# 04_DragonBoard_INTF.net
KiCad netlist of a schematic drawn in Altium Designer
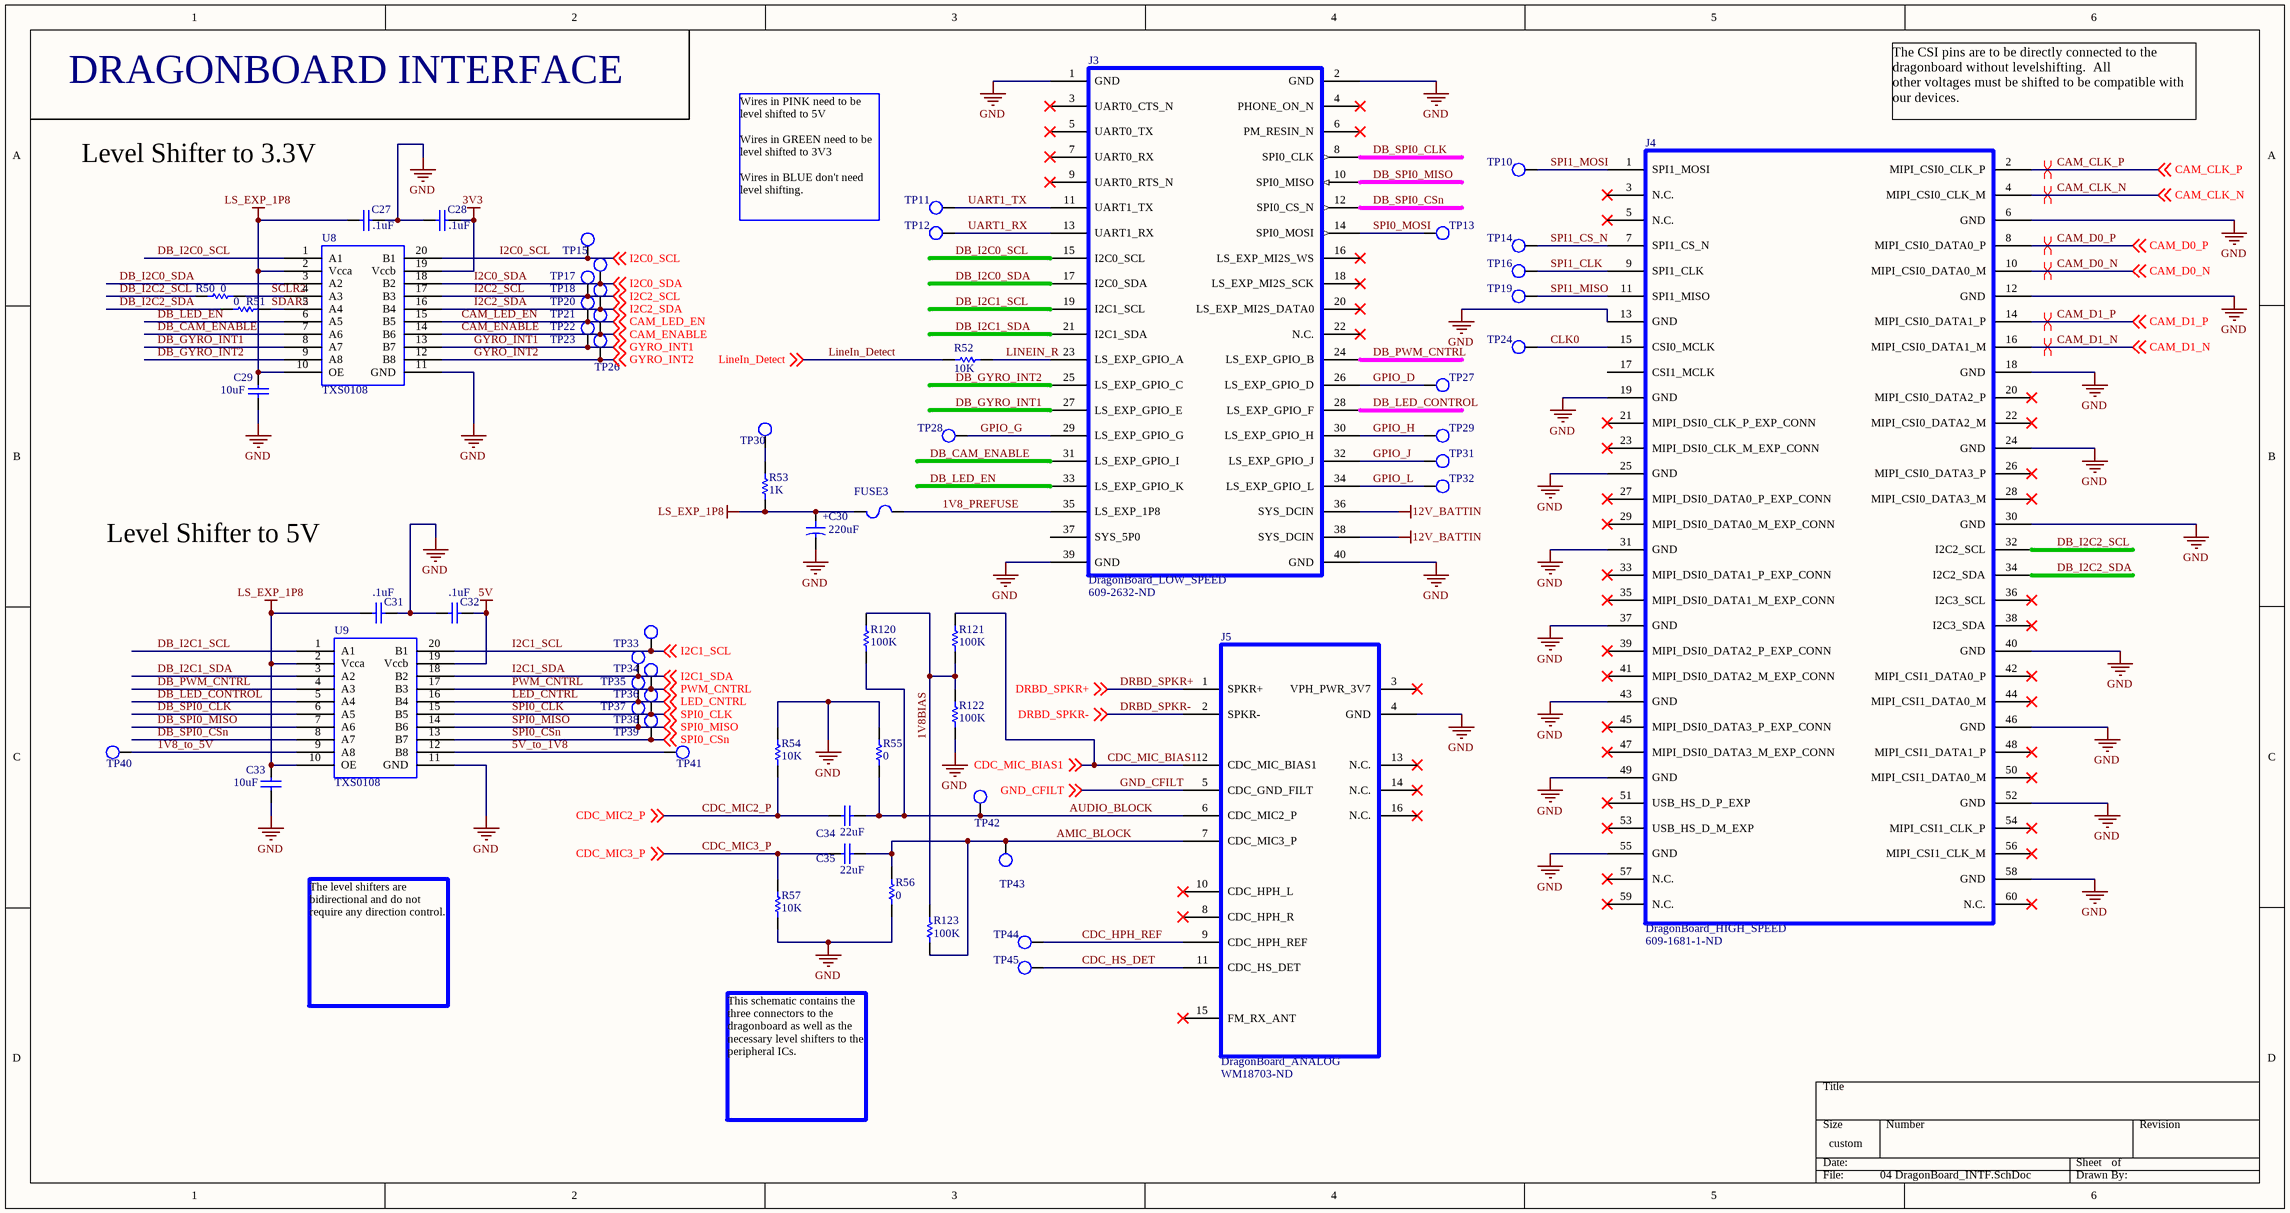
[diagram p0: 04 DragonBoard_INTF.SchDoc]

(export (version "E")
  (design (tool "Eeschema 10.0.6"))
  (components
    (comp (ref "C27")
      (value ".1uF")
      (footprint "CAPC2012X135N")
      (description "Cap Ceramic 0.1uF 250V X7T 10% SMD 0805 125C Plastic T/R")
      (fields
        (field (name "MANUFACTURER") "TDK")
        (field (name "MANUFACTURER PART NUMBER") "C2012X7T2E104K125AE")
      )
      (libsource (lib "schlib_truman") (part "CAP_0805_.1u_250V"))
    )
    (comp (ref "C28")
      (value ".1uF")
      (footprint "CAPC2012X135N")
      (description "Cap Ceramic 0.1uF 250V X7T 10% SMD 0805 125C Plastic T/R")
      (fields
        (field (name "MANUFACTURER") "TDK")
        (field (name "MANUFACTURER PART NUMBER") "C2012X7T2E104K125AE")
      )
      (libsource (lib "schlib_truman") (part "CAP_0805_.1u_250V"))
    )
    (comp (ref "C29")
      (value "10uF")
      (footprint "CAPC2012X135N")
      (description "Cap Ceramic 10uF 16V X5R 10% SMD 0805 85C T/R")
      (fields
        (field (name "MANUFACTURER") "Johanson Dielectrics")
        (field (name "MANUFACTURER PART NUMBER") "160R15X106KV4E")
      )
      (libsource (lib "schlib_truman") (part "CAP_0805_10u_16V"))
    )
    (comp (ref "C30")
      (value "CAP ALUM 220UF 20% 25V SMD")
      (footprint "CAP_RADIAL")
      (fields
        (field (name "MANUFACTURER") "Nichicon")
        (field (name "MANUFACTURER PART NUMBER") "UWT1E221MNL1GS")
        (field (name "TOLERANCE") "20%")
        (field (name "CAPACITANCE") "220uF")
      )
      (libsource (lib "schlib_truman") (part "CAP_RAD_220u_25V"))
    )
    (comp (ref "C31")
      (value ".1uF")
      (footprint "CAPC2012X135N")
      (description "Cap Ceramic 0.1uF 250V X7T 10% SMD 0805 125C Plastic T/R")
      (fields
        (field (name "MANUFACTURER") "TDK")
        (field (name "MANUFACTURER PART NUMBER") "C2012X7T2E104K125AE")
      )
      (libsource (lib "schlib_truman") (part "CAP_0805_.1u_250V"))
    )
    (comp (ref "C32")
      (value ".1uF")
      (footprint "CAPC2012X135N")
      (description "Cap Ceramic 0.1uF 250V X7T 10% SMD 0805 125C Plastic T/R")
      (fields
        (field (name "MANUFACTURER") "TDK")
        (field (name "MANUFACTURER PART NUMBER") "C2012X7T2E104K125AE")
      )
      (libsource (lib "schlib_truman") (part "CAP_0805_.1u_250V"))
    )
    (comp (ref "C33")
      (value "10uF")
      (footprint "CAPC2012X135N")
      (description "Cap Ceramic 10uF 16V X5R 10% SMD 0805 85C T/R")
      (fields
        (field (name "MANUFACTURER") "Johanson Dielectrics")
        (field (name "MANUFACTURER PART NUMBER") "160R15X106KV4E")
      )
      (libsource (lib "schlib_truman") (part "CAP_0805_10u_16V"))
    )
    (comp (ref "C34")
      (value "22uF")
      (footprint "CAPC2012X135N")
      (fields
        (field (name "MANUFACTURER") "Samsung")
        (field (name "MANUFACTURER PART NUMBER") "CL21A226MAQNNNE")
        (field (name "TOLERANCE") "20%")
      )
      (libsource (lib "schlib_truman") (part "CAP_0805_22u_25V"))
    )
    (comp (ref "C35")
      (value "22uF")
      (footprint "CAPC2012X135N")
      (fields
        (field (name "MANUFACTURER") "Samsung")
        (field (name "MANUFACTURER PART NUMBER") "CL21A226MAQNNNE")
        (field (name "TOLERANCE") "20%")
      )
      (libsource (lib "schlib_truman") (part "CAP_0805_22u_25V"))
    )
    (comp (ref "FUSE3")
      (value "FUSE_0805_1A_32VDC")
      (footprint "RES0805")
      (description "FUSE 1.00A 0805 VFAST SMD")
      (fields
        (field (name "MANUFACTURER") "Vishay")
        (field (name "MANUFACTURER PART NUMBER") "MFU0805FF01000P100")
      )
      (libsource (lib "schlib_truman") (part "FUSE_0805_1A_32VDC"))
    )
    (comp (ref "J3")
      (value "DragonBoard_LOW_SPEED")
      (footprint "57202_40_PIN_HEADER")
      (description "40 Positions Header, Unshrouded Connector 0.079\" (2.00mm) Surface Mount Gold, GXT™")
      (fields
        (field (name "MANUFACTURER") "Amphenol FCI")
        (field (name "MANUFACTURER PART NUMBER") "57202-G52-20LF")
        (field (name "SUPPLIER PART NUMBER 1") "609-2632-ND")
      )
      (libsource (lib "schlib_truman") (part "DragonBoard_LOW_SPEED"))
    )
    (comp (ref "J4")
      (value "DragonBoard_HIGH_SPEED")
      (footprint "DB_HIGH_SPEED")
      (description "60 Position Connector Plug, Center Strip Contacts Surface Mount Gold")
      (fields
        (field (name "MANUFACTURER") "Amphenol FCI")
        (field (name "MANUFACTURER PART NUMBER") "61083-064402LF")
        (field (name "SUPPLIER PART NUMBER 1") "609-1681-1-ND")
      )
      (libsource (lib "schlib_truman") (part "DragonBoard_HIGH_SPEED"))
    )
    (comp (ref "J5")
      (value "DragonBoard_ANALOG")
      (footprint "16_PIN_ANALOG_CONN")
      (description "Conn Socket Strip RCP 16 POS 2mm Solder ST SMD Tube")
      (fields
        (field (name "MANUFACTURER") "Molex")
        (field (name "MANUFACTURER PART NUMBER") "0791091007")
        (field (name "SUPPLIER PART NUMBER 1") "WM18703-ND")
      )
      (libsource (lib "schlib_truman") (part "DragonBoard_ANALOG"))
    )
    (comp (ref "R50")
      (value "RES_0805_JMP")
      (footprint "RES0805")
      (description "RES, THICK FILM, 0R, 0.125W, 0805")
      (fields
        (field (name "MANUFACTURER") "Yageo")
        (field (name "MANUFACTURER PART NUMBER") "RC0805JR-070RL")
        (field (name "ALTIUM_UNNAMED_1") "0")
      )
      (libsource (lib "schlib_truman") (part "RES_0805_JMP"))
    )
    (comp (ref "R51")
      (value "RES_0805_JMP")
      (footprint "RES0805")
      (description "RES, THICK FILM, 0R, 0.125W, 0805")
      (fields
        (field (name "MANUFACTURER") "Yageo")
        (field (name "MANUFACTURER PART NUMBER") "RC0805JR-070RL")
        (field (name "ALTIUM_UNNAMED_1") "0")
      )
      (libsource (lib "schlib_truman") (part "RES_0805_JMP"))
    )
    (comp (ref "R52")
      (value "RES_0805_10K")
      (footprint "RES0805")
      (description "RES, THICK FILM, 10K, 5%, 0.125W, 0805")
      (fields
        (field (name "MANUFACTURER") "Yageo")
        (field (name "MANUFACTURER PART NUMBER") "RC0805JR-0710KL")
        (field (name "RESISTANCE") "10K")
      )
      (libsource (lib "schlib_truman") (part "RES_0805_10K"))
    )
    (comp (ref "R53")
      (value "RES_0805_1K")
      (footprint "RES0805")
      (description "RES SMD 1K OHM 1% 1/8W 0805")
      (fields
        (field (name "MANUFACTURER") "Yageo")
        (field (name "MANUFACTURER PART NUMBER") "RC0805FR-071KL")
        (field (name "ALTIUM_UNNAMED_1") "1K")
      )
      (libsource (lib "schlib_truman") (part "RES_0805_1K"))
    )
    (comp (ref "R54")
      (value "RES_0805_10K")
      (footprint "RES0805")
      (description "RES, THICK FILM, 10K, 5%, 0.125W, 0805")
      (fields
        (field (name "MANUFACTURER") "Yageo")
        (field (name "MANUFACTURER PART NUMBER") "RC0805JR-0710KL")
        (field (name "RESISTANCE") "10K")
      )
      (libsource (lib "schlib_truman") (part "RES_0805_10K"))
    )
    (comp (ref "R55")
      (value "RES_0805_JMP")
      (footprint "RES0805")
      (description "RES, THICK FILM, 0R, 0.125W, 0805")
      (fields
        (field (name "MANUFACTURER") "Yageo")
        (field (name "MANUFACTURER PART NUMBER") "RC0805JR-070RL")
        (field (name "ALTIUM_UNNAMED_1") "0")
      )
      (libsource (lib "schlib_truman") (part "RES_0805_JMP"))
    )
    (comp (ref "R56")
      (value "RES_0805_JMP")
      (footprint "RES0805")
      (description "RES, THICK FILM, 0R, 0.125W, 0805")
      (fields
        (field (name "MANUFACTURER") "Yageo")
        (field (name "MANUFACTURER PART NUMBER") "RC0805JR-070RL")
        (field (name "ALTIUM_UNNAMED_1") "0")
      )
      (libsource (lib "schlib_truman") (part "RES_0805_JMP"))
    )
    (comp (ref "R57")
      (value "RES_0805_10K")
      (footprint "RES0805")
      (description "RES, THICK FILM, 10K, 5%, 0.125W, 0805")
      (fields
        (field (name "MANUFACTURER") "Yageo")
        (field (name "MANUFACTURER PART NUMBER") "RC0805JR-0710KL")
        (field (name "RESISTANCE") "10K")
      )
      (libsource (lib "schlib_truman") (part "RES_0805_10K"))
    )
    (comp (ref "R120")
      (value "RES_0805_100K")
      (footprint "RES0805")
      (description "Res Thick Film 0805 100K Ohm 1% 0.125W(1/8W) ±100ppm/C Molded SMD Automotive Punched T/R")
      (fields
        (field (name "MANUFACTURER") "Panasonic ECG")
        (field (name "MANUFACTURER PART NUMBER") "ERJ-6ENF1003V")
        (field (name "ALTIUM_UNNAMED_1") "100K")
      )
      (libsource (lib "schlib_truman") (part "RES_0805_100K"))
    )
    (comp (ref "R121")
      (value "RES_0805_100K")
      (footprint "RES0805")
      (description "Res Thick Film 0805 100K Ohm 1% 0.125W(1/8W) ±100ppm/C Molded SMD Automotive Punched T/R")
      (fields
        (field (name "MANUFACTURER") "Panasonic ECG")
        (field (name "MANUFACTURER PART NUMBER") "ERJ-6ENF1003V")
        (field (name "ALTIUM_UNNAMED_1") "100K")
      )
      (libsource (lib "schlib_truman") (part "RES_0805_100K"))
    )
    (comp (ref "R122")
      (value "RES_0805_100K")
      (footprint "RES0805")
      (description "Res Thick Film 0805 100K Ohm 1% 0.125W(1/8W) ±100ppm/C Molded SMD Automotive Punched T/R")
      (fields
        (field (name "MANUFACTURER") "Panasonic ECG")
        (field (name "MANUFACTURER PART NUMBER") "ERJ-6ENF1003V")
        (field (name "ALTIUM_UNNAMED_1") "100K")
      )
      (libsource (lib "schlib_truman") (part "RES_0805_100K"))
    )
    (comp (ref "R123")
      (value "RES_0805_100K")
      (footprint "RES0805")
      (description "Res Thick Film 0805 100K Ohm 1% 0.125W(1/8W) ±100ppm/C Molded SMD Automotive Punched T/R")
      (fields
        (field (name "MANUFACTURER") "Panasonic ECG")
        (field (name "MANUFACTURER PART NUMBER") "ERJ-6ENF1003V")
        (field (name "ALTIUM_UNNAMED_1") "100K")
      )
      (libsource (lib "schlib_truman") (part "RES_0805_100K"))
    )
    (comp (ref "TP10")
      (value "TP")
      (footprint "TestPoint_0805")
      (description "Testpoint_0805")
      (fields
        (field (name "MANUFACTURER") "TE Connectivity")
        (field (name "MANUFACTURER PART NUMBER") "1625854-2")
      )
      (libsource (lib "schlib_truman") (part "TP"))
    )
    (comp (ref "TP11")
      (value "TP")
      (footprint "TestPoint_0805")
      (description "Testpoint_0805")
      (fields
        (field (name "MANUFACTURER") "TE Connectivity")
        (field (name "MANUFACTURER PART NUMBER") "1625854-2")
      )
      (libsource (lib "schlib_truman") (part "TP"))
    )
    (comp (ref "TP12")
      (value "TP")
      (footprint "TestPoint_0805")
      (description "Testpoint_0805")
      (fields
        (field (name "MANUFACTURER") "TE Connectivity")
        (field (name "MANUFACTURER PART NUMBER") "1625854-2")
      )
      (libsource (lib "schlib_truman") (part "TP"))
    )
    (comp (ref "TP13")
      (value "TP")
      (footprint "TestPoint_0805")
      (description "Testpoint_0805")
      (fields
        (field (name "MANUFACTURER") "TE Connectivity")
        (field (name "MANUFACTURER PART NUMBER") "1625854-2")
      )
      (libsource (lib "schlib_truman") (part "TP"))
    )
    (comp (ref "TP14")
      (value "TP")
      (footprint "TestPoint_0805")
      (description "Testpoint_0805")
      (fields
        (field (name "MANUFACTURER") "TE Connectivity")
        (field (name "MANUFACTURER PART NUMBER") "1625854-2")
      )
      (libsource (lib "schlib_truman") (part "TP"))
    )
    (comp (ref "TP15")
      (value "TP")
      (footprint "TestPoint_0805")
      (description "Testpoint_0805")
      (fields
        (field (name "MANUFACTURER") "TE Connectivity")
        (field (name "MANUFACTURER PART NUMBER") "1625854-2")
      )
      (libsource (lib "schlib_truman") (part "TP"))
    )
    (comp (ref "TP16")
      (value "TP")
      (footprint "TestPoint_0805")
      (description "Testpoint_0805")
      (fields
        (field (name "MANUFACTURER") "TE Connectivity")
        (field (name "MANUFACTURER PART NUMBER") "1625854-2")
      )
      (libsource (lib "schlib_truman") (part "TP"))
    )
    (comp (ref "TP17")
      (value "TP")
      (footprint "TestPoint_0805")
      (description "Testpoint_0805")
      (fields
        (field (name "MANUFACTURER") "TE Connectivity")
        (field (name "MANUFACTURER PART NUMBER") "1625854-2")
      )
      (libsource (lib "schlib_truman") (part "TP"))
    )
    (comp (ref "TP18")
      (value "TP")
      (footprint "TestPoint_0805")
      (description "Testpoint_0805")
      (fields
        (field (name "MANUFACTURER") "TE Connectivity")
        (field (name "MANUFACTURER PART NUMBER") "1625854-2")
      )
      (libsource (lib "schlib_truman") (part "TP"))
    )
    (comp (ref "TP19")
      (value "TP")
      (footprint "TestPoint_0805")
      (description "Testpoint_0805")
      (fields
        (field (name "MANUFACTURER") "TE Connectivity")
        (field (name "MANUFACTURER PART NUMBER") "1625854-2")
      )
      (libsource (lib "schlib_truman") (part "TP"))
    )
    (comp (ref "TP20")
      (value "TP")
      (footprint "TestPoint_0805")
      (description "Testpoint_0805")
      (fields
        (field (name "MANUFACTURER") "TE Connectivity")
        (field (name "MANUFACTURER PART NUMBER") "1625854-2")
      )
      (libsource (lib "schlib_truman") (part "TP"))
    )
    (comp (ref "TP21")
      (value "TP")
      (footprint "TestPoint_0805")
      (description "Testpoint_0805")
      (fields
        (field (name "MANUFACTURER") "TE Connectivity")
        (field (name "MANUFACTURER PART NUMBER") "1625854-2")
      )
      (libsource (lib "schlib_truman") (part "TP"))
    )
    (comp (ref "TP22")
      (value "TP")
      (footprint "TestPoint_0805")
      (description "Testpoint_0805")
      (fields
        (field (name "MANUFACTURER") "TE Connectivity")
        (field (name "MANUFACTURER PART NUMBER") "1625854-2")
      )
      (libsource (lib "schlib_truman") (part "TP"))
    )
    (comp (ref "TP23")
      (value "TP")
      (footprint "TestPoint_0805")
      (description "Testpoint_0805")
      (fields
        (field (name "MANUFACTURER") "TE Connectivity")
        (field (name "MANUFACTURER PART NUMBER") "1625854-2")
      )
      (libsource (lib "schlib_truman") (part "TP"))
    )
    (comp (ref "TP24")
      (value "TP")
      (footprint "TestPoint_0805")
      (description "Testpoint_0805")
      (fields
        (field (name "MANUFACTURER") "TE Connectivity")
        (field (name "MANUFACTURER PART NUMBER") "1625854-2")
      )
      (libsource (lib "schlib_truman") (part "TP"))
    )
    (comp (ref "TP26")
      (value "TP")
      (footprint "TestPoint_0805")
      (description "Testpoint_0805")
      (fields
        (field (name "MANUFACTURER") "TE Connectivity")
        (field (name "MANUFACTURER PART NUMBER") "1625854-2")
      )
      (libsource (lib "schlib_truman") (part "TP"))
    )
    (comp (ref "TP27")
      (value "TP")
      (footprint "TestPoint_0805")
      (description "Testpoint_0805")
      (fields
        (field (name "MANUFACTURER") "TE Connectivity")
        (field (name "MANUFACTURER PART NUMBER") "1625854-2")
      )
      (libsource (lib "schlib_truman") (part "TP"))
    )
    (comp (ref "TP28")
      (value "TP")
      (footprint "TestPoint_0805")
      (description "Testpoint_0805")
      (fields
        (field (name "MANUFACTURER") "TE Connectivity")
        (field (name "MANUFACTURER PART NUMBER") "1625854-2")
      )
      (libsource (lib "schlib_truman") (part "TP"))
    )
    (comp (ref "TP29")
      (value "TP")
      (footprint "TestPoint_0805")
      (description "Testpoint_0805")
      (fields
        (field (name "MANUFACTURER") "TE Connectivity")
        (field (name "MANUFACTURER PART NUMBER") "1625854-2")
      )
      (libsource (lib "schlib_truman") (part "TP"))
    )
    (comp (ref "TP30")
      (value "TP")
      (footprint "TestPoint_0805")
      (description "Testpoint_0805")
      (fields
        (field (name "MANUFACTURER") "TE Connectivity")
        (field (name "MANUFACTURER PART NUMBER") "1625854-2")
      )
      (libsource (lib "schlib_truman") (part "TP"))
    )
    (comp (ref "TP31")
      (value "TP")
      (footprint "TestPoint_0805")
      (description "Testpoint_0805")
      (fields
        (field (name "MANUFACTURER") "TE Connectivity")
        (field (name "MANUFACTURER PART NUMBER") "1625854-2")
      )
      (libsource (lib "schlib_truman") (part "TP"))
    )
    (comp (ref "TP32")
      (value "TP")
      (footprint "TestPoint_0805")
      (description "Testpoint_0805")
      (fields
        (field (name "MANUFACTURER") "TE Connectivity")
        (field (name "MANUFACTURER PART NUMBER") "1625854-2")
      )
      (libsource (lib "schlib_truman") (part "TP"))
    )
    (comp (ref "TP33")
      (value "TP")
      (footprint "TestPoint_0805")
      (description "Testpoint_0805")
      (fields
        (field (name "MANUFACTURER") "TE Connectivity")
        (field (name "MANUFACTURER PART NUMBER") "1625854-2")
      )
      (libsource (lib "schlib_truman") (part "TP"))
    )
    (comp (ref "TP34")
      (value "TP")
      (footprint "TestPoint_0805")
      (description "Testpoint_0805")
      (fields
        (field (name "MANUFACTURER") "TE Connectivity")
        (field (name "MANUFACTURER PART NUMBER") "1625854-2")
      )
      (libsource (lib "schlib_truman") (part "TP"))
    )
    (comp (ref "TP35")
      (value "TP")
      (footprint "TestPoint_0805")
      (description "Testpoint_0805")
      (fields
        (field (name "MANUFACTURER") "TE Connectivity")
        (field (name "MANUFACTURER PART NUMBER") "1625854-2")
      )
      (libsource (lib "schlib_truman") (part "TP"))
    )
    (comp (ref "TP36")
      (value "TP")
      (footprint "TestPoint_0805")
      (description "Testpoint_0805")
      (fields
        (field (name "MANUFACTURER") "TE Connectivity")
        (field (name "MANUFACTURER PART NUMBER") "1625854-2")
      )
      (libsource (lib "schlib_truman") (part "TP"))
    )
    (comp (ref "TP37")
      (value "TP")
      (footprint "TestPoint_0805")
      (description "Testpoint_0805")
      (fields
        (field (name "MANUFACTURER") "TE Connectivity")
        (field (name "MANUFACTURER PART NUMBER") "1625854-2")
      )
      (libsource (lib "schlib_truman") (part "TP"))
    )
    (comp (ref "TP38")
      (value "TP")
      (footprint "TestPoint_0805")
      (description "Testpoint_0805")
      (fields
        (field (name "MANUFACTURER") "TE Connectivity")
        (field (name "MANUFACTURER PART NUMBER") "1625854-2")
      )
      (libsource (lib "schlib_truman") (part "TP"))
    )
    (comp (ref "TP39")
      (value "TP")
      (footprint "TestPoint_0805")
      (description "Testpoint_0805")
      (fields
        (field (name "MANUFACTURER") "TE Connectivity")
        (field (name "MANUFACTURER PART NUMBER") "1625854-2")
      )
      (libsource (lib "schlib_truman") (part "TP"))
    )
    (comp (ref "TP40")
      (value "TP")
      (footprint "TestPoint_0805")
      (description "Testpoint_0805")
      (fields
        (field (name "MANUFACTURER") "TE Connectivity")
        (field (name "MANUFACTURER PART NUMBER") "1625854-2")
      )
      (libsource (lib "schlib_truman") (part "TP"))
    )
    (comp (ref "TP41")
      (value "TP")
      (footprint "TestPoint_0805")
      (description "Testpoint_0805")
      (fields
        (field (name "MANUFACTURER") "TE Connectivity")
        (field (name "MANUFACTURER PART NUMBER") "1625854-2")
      )
      (libsource (lib "schlib_truman") (part "TP"))
    )
    (comp (ref "TP42")
      (value "TP")
      (footprint "TestPoint_0805")
      (description "Testpoint_0805")
      (fields
        (field (name "MANUFACTURER") "TE Connectivity")
        (field (name "MANUFACTURER PART NUMBER") "1625854-2")
      )
      (libsource (lib "schlib_truman") (part "TP"))
    )
    (comp (ref "TP43")
      (value "TP")
      (footprint "TestPoint_0805")
      (description "Testpoint_0805")
      (fields
        (field (name "MANUFACTURER") "TE Connectivity")
        (field (name "MANUFACTURER PART NUMBER") "1625854-2")
      )
      (libsource (lib "schlib_truman") (part "TP"))
    )
    (comp (ref "TP44")
      (value "TP")
      (footprint "TestPoint_0805")
      (description "Testpoint_0805")
      (fields
        (field (name "MANUFACTURER") "TE Connectivity")
        (field (name "MANUFACTURER PART NUMBER") "1625854-2")
      )
      (libsource (lib "schlib_truman") (part "TP"))
    )
    (comp (ref "TP45")
      (value "TP")
      (footprint "TestPoint_0805")
      (description "Testpoint_0805")
      (fields
        (field (name "MANUFACTURER") "TE Connectivity")
        (field (name "MANUFACTURER PART NUMBER") "1625854-2")
      )
      (libsource (lib "schlib_truman") (part "TP"))
    )
    (comp (ref "U8")
      (value "TXS0108")
      (footprint "TSSOP20")
      (description "TRANSLATOR, VOLTAGE, 8BIT, 20TSSOP")
      (fields
        (field (name "MANUFACTURER") "Texas Instruments")
        (field (name "MANUFACTURER PART NUMBER") "TXS0108EPWR")
      )
      (libsource (lib "schlib_truman") (part "TXS0108"))
    )
    (comp (ref "U9")
      (value "TXS0108")
      (footprint "TSSOP20")
      (description "TRANSLATOR, VOLTAGE, 8BIT, 20TSSOP")
      (fields
        (field (name "MANUFACTURER") "Texas Instruments")
        (field (name "MANUFACTURER PART NUMBER") "TXS0108EPWR")
      )
      (libsource (lib "schlib_truman") (part "TXS0108"))
    )
  )
  (nets
    (net (code "1") (name "/1V8BIAS") (class "Default")
      (node (ref "R120") (pin "2") (pinfunction "2_2") (pintype "passive"))
      (node (ref "R121") (pin "1") (pinfunction "1_1") (pintype "passive"))
      (node (ref "R122") (pin "2") (pinfunction "2_2") (pintype "passive"))
      (node (ref "R123") (pin "2") (pinfunction "2_2") (pintype "passive"))
    )
    (net (code "2") (name "/1V8_PREFUSE") (class "Default")
      (node (ref "FUSE3") (pin "2") (pinfunction "2_2") (pintype "passive"))
      (node (ref "J3") (pin "35") (pinfunction "LS_EXP_1P8_35") (pintype "passive"))
    )
    (net (code "3") (name "/1V8_to_5V") (class "Default")
      (node (ref "TP40") (pin "1") (pintype "passive"))
      (node (ref "U9") (pin "9") (pinfunction "A8_9") (pintype "passive"))
    )
    (net (code "4") (name "/5V_to_1V8") (class "Default")
      (node (ref "TP41") (pin "1") (pintype "passive"))
      (node (ref "U9") (pin "12") (pinfunction "B8_12") (pintype "passive"))
    )
    (net (code "5") (name "/AMIC_BLOCK") (class "Default")
      (node (ref "C35") (pin "2") (pinfunction "2_2") (pintype "passive"))
      (node (ref "J5") (pin "7") (pinfunction "CDC_MIC3_P_7") (pintype "passive"))
      (node (ref "R123") (pin "1") (pinfunction "1_1") (pintype "passive"))
      (node (ref "R56") (pin "2") (pinfunction "2_2") (pintype "passive"))
      (node (ref "TP43") (pin "1") (pintype "passive"))
    )
    (net (code "6") (name "/AUDIO_BLOCK") (class "Default")
      (node (ref "C34") (pin "2") (pinfunction "2_2") (pintype "passive"))
      (node (ref "J5") (pin "6") (pinfunction "CDC_MIC2_P_6") (pintype "passive"))
      (node (ref "R120") (pin "1") (pinfunction "1_1") (pintype "passive"))
      (node (ref "R55") (pin "1") (pinfunction "1_1") (pintype "passive"))
      (node (ref "TP42") (pin "1") (pintype "passive"))
    )
    (net (code "7") (name "/CDC_HPH_REF") (class "Default")
      (node (ref "J5") (pin "9") (pinfunction "CDC_HPH_REF_9") (pintype "passive"))
      (node (ref "TP44") (pin "1") (pintype "passive"))
    )
    (net (code "8") (name "/CDC_HS_DET") (class "Default")
      (node (ref "J5") (pin "11") (pinfunction "CDC_HS_DET_11") (pintype "passive"))
      (node (ref "TP45") (pin "1") (pintype "passive"))
    )
    (net (code "9") (name "/CLK0") (class "Default")
      (node (ref "J4") (pin "15") (pinfunction "CSI0_MCLK_15") (pintype "passive"))
      (node (ref "TP24") (pin "1") (pintype "passive"))
    )
    (net (code "10") (name "/DB_CAM_ENABLE") (class "Default")
      (node (ref "J3") (pin "31") (pinfunction "LS_EXP_GPIO_I_31") (pintype "passive"))
      (node (ref "U8") (pin "7") (pinfunction "A6_7") (pintype "passive"))
    )
    (net (code "11") (name "/DB_GYRO_INT1") (class "Default")
      (node (ref "J3") (pin "27") (pinfunction "LS_EXP_GPIO_E_27") (pintype "passive"))
      (node (ref "U8") (pin "8") (pinfunction "A7_8") (pintype "passive"))
    )
    (net (code "12") (name "/DB_GYRO_INT2") (class "Default")
      (node (ref "J3") (pin "25") (pinfunction "LS_EXP_GPIO_C_25") (pintype "passive"))
      (node (ref "U8") (pin "9") (pinfunction "A8_9") (pintype "passive"))
    )
    (net (code "13") (name "/DB_I2C0_SCL") (class "Default")
      (node (ref "J3") (pin "15") (pinfunction "I2C0_SCL_15") (pintype "passive"))
      (node (ref "U8") (pin "1") (pinfunction "A1_1") (pintype "passive"))
    )
    (net (code "14") (name "/DB_I2C0_SDA") (class "Default")
      (node (ref "J3") (pin "17") (pinfunction "I2C0_SDA_17") (pintype "passive"))
      (node (ref "U8") (pin "3") (pinfunction "A2_3") (pintype "passive"))
    )
    (net (code "15") (name "/DB_I2C1_SCL") (class "Default")
      (node (ref "J3") (pin "19") (pinfunction "I2C1_SCL_19") (pintype "passive"))
      (node (ref "U9") (pin "1") (pinfunction "A1_1") (pintype "passive"))
    )
    (net (code "16") (name "/DB_I2C1_SDA") (class "Default")
      (node (ref "J3") (pin "21") (pinfunction "I2C1_SDA_21") (pintype "passive"))
      (node (ref "U9") (pin "3") (pinfunction "A2_3") (pintype "passive"))
    )
    (net (code "17") (name "/DB_I2C2_SCL") (class "Default")
      (node (ref "J4") (pin "32") (pinfunction "I2C2_SCL_32") (pintype "passive"))
      (node (ref "R50") (pin "1") (pinfunction "1_1") (pintype "passive"))
    )
    (net (code "18") (name "/DB_I2C2_SDA") (class "Default")
      (node (ref "J4") (pin "34") (pinfunction "I2C2_SDA_34") (pintype "passive"))
      (node (ref "R51") (pin "1") (pinfunction "1_1") (pintype "passive"))
    )
    (net (code "19") (name "/DB_LED_CONTROL") (class "Default")
      (node (ref "J3") (pin "28") (pinfunction "LS_EXP_GPIO_F_28") (pintype "passive"))
      (node (ref "U9") (pin "5") (pinfunction "A4_5") (pintype "passive"))
    )
    (net (code "20") (name "/DB_LED_EN") (class "Default")
      (node (ref "J3") (pin "33") (pinfunction "LS_EXP_GPIO_K_33") (pintype "passive"))
      (node (ref "U8") (pin "6") (pinfunction "A5_6") (pintype "passive"))
    )
    (net (code "21") (name "/DB_PWM_CNTRL") (class "Default")
      (node (ref "J3") (pin "24") (pinfunction "LS_EXP_GPIO_B_24") (pintype "passive"))
      (node (ref "U9") (pin "4") (pinfunction "A3_4") (pintype "passive"))
    )
    (net (code "22") (name "/DB_SPI0_CLK") (class "Default")
      (node (ref "J3") (pin "8") (pinfunction "SPI0_CLK_8") (pintype "output"))
      (node (ref "U9") (pin "6") (pinfunction "A5_6") (pintype "passive"))
    )
    (net (code "23") (name "/DB_SPI0_CSn") (class "Default")
      (node (ref "J3") (pin "12") (pinfunction "SPI0_CS_N_12") (pintype "output"))
      (node (ref "U9") (pin "8") (pinfunction "A7_8") (pintype "passive"))
    )
    (net (code "24") (name "/DB_SPI0_MISO") (class "Default")
      (node (ref "J3") (pin "10") (pinfunction "SPI0_MISO_10") (pintype "input"))
      (node (ref "U9") (pin "7") (pinfunction "A6_7") (pintype "passive"))
    )
    (net (code "25") (name "/GPIO_D") (class "Default")
      (node (ref "J3") (pin "26") (pinfunction "LS_EXP_GPIO_D_26") (pintype "passive"))
      (node (ref "TP27") (pin "1") (pintype "passive"))
    )
    (net (code "26") (name "/GPIO_G") (class "Default")
      (node (ref "J3") (pin "29") (pinfunction "LS_EXP_GPIO_G_29") (pintype "passive"))
      (node (ref "TP28") (pin "1") (pintype "passive"))
    )
    (net (code "27") (name "/GPIO_H") (class "Default")
      (node (ref "J3") (pin "30") (pinfunction "LS_EXP_GPIO_H_30") (pintype "passive"))
      (node (ref "TP29") (pin "1") (pintype "passive"))
    )
    (net (code "28") (name "/GPIO_J") (class "Default")
      (node (ref "J3") (pin "32") (pinfunction "LS_EXP_GPIO_J_32") (pintype "passive"))
      (node (ref "TP31") (pin "1") (pintype "passive"))
    )
    (net (code "29") (name "/GPIO_L") (class "Default")
      (node (ref "J3") (pin "34") (pinfunction "LS_EXP_GPIO_L_34") (pintype "passive"))
      (node (ref "TP32") (pin "1") (pintype "passive"))
    )
    (net (code "30") (name "/LINEIN_R") (class "Default")
      (node (ref "J3") (pin "23") (pinfunction "LS_EXP_GPIO_A_23") (pintype "passive"))
      (node (ref "R52") (pin "2") (pinfunction "2_2") (pintype "passive"))
    )
    (net (code "31") (name "/SCLR2") (class "Default")
      (node (ref "R50") (pin "2") (pinfunction "2_2") (pintype "passive"))
      (node (ref "U8") (pin "4") (pinfunction "A3_4") (pintype "passive"))
    )
    (net (code "32") (name "/SDAR2") (class "Default")
      (node (ref "R51") (pin "2") (pinfunction "2_2") (pintype "passive"))
      (node (ref "U8") (pin "5") (pinfunction "A4_5") (pintype "passive"))
    )
    (net (code "33") (name "/SPI0_MOSI") (class "Default")
      (node (ref "J3") (pin "14") (pinfunction "SPI0_MOSI_14") (pintype "output"))
      (node (ref "TP13") (pin "1") (pintype "passive"))
    )
    (net (code "34") (name "/SPI1_CLK") (class "Default")
      (node (ref "J4") (pin "9") (pinfunction "SPI1_CLK_9") (pintype "passive"))
      (node (ref "TP16") (pin "1") (pintype "passive"))
    )
    (net (code "35") (name "/SPI1_CS_N") (class "Default")
      (node (ref "J4") (pin "7") (pinfunction "SPI1_CS_N_7") (pintype "passive"))
      (node (ref "TP14") (pin "1") (pintype "passive"))
    )
    (net (code "36") (name "/SPI1_MISO") (class "Default")
      (node (ref "J4") (pin "11") (pinfunction "SPI1_MISO_11") (pintype "passive"))
      (node (ref "TP19") (pin "1") (pintype "passive"))
    )
    (net (code "37") (name "/SPI1_MOSI") (class "Default")
      (node (ref "J4") (pin "1") (pinfunction "SPI1_MOSI_1") (pintype "passive"))
      (node (ref "TP10") (pin "1") (pintype "passive"))
    )
    (net (code "38") (name "/UART1_RX") (class "Default")
      (node (ref "J3") (pin "13") (pinfunction "UART1_RX_13") (pintype "passive"))
      (node (ref "TP12") (pin "1") (pintype "passive"))
    )
    (net (code "39") (name "/UART1_TX") (class "Default")
      (node (ref "J3") (pin "11") (pinfunction "UART1_TX_11") (pintype "passive"))
      (node (ref "TP11") (pin "1") (pintype "passive"))
    )
    (net (code "40") (name "3V3") (class "Default")
      (node (ref "C28") (pin "2") (pinfunction "2_2") (pintype "passive"))
      (node (ref "U8") (pin "19") (pinfunction "Vccb_19") (pintype "passive"))
    )
    (net (code "41") (name "5V") (class "Default")
      (node (ref "C32") (pin "2") (pinfunction "2_2") (pintype "passive"))
      (node (ref "U9") (pin "19") (pinfunction "Vccb_19") (pintype "passive"))
    )
    (net (code "42") (name "12V_BATTIN") (class "Default")
      (node (ref "J3") (pin "36") (pinfunction "SYS_DCIN_36") (pintype "passive"))
      (node (ref "J3") (pin "38") (pinfunction "SYS_DCIN_38") (pintype "passive"))
    )
    (net (code "43") (name "CAM_CLK_N") (class "Default")
      (node (ref "J4") (pin "4") (pinfunction "MIPI_CSI0_CLK_M_4") (pintype "passive"))
    )
    (net (code "44") (name "CAM_CLK_P") (class "Default")
      (node (ref "J4") (pin "2") (pinfunction "MIPI_CSI0_CLK_P_2") (pintype "passive"))
    )
    (net (code "45") (name "CAM_D0_N") (class "Default")
      (node (ref "J4") (pin "10") (pinfunction "MIPI_CSI0_DATA0_M_10") (pintype "passive"))
    )
    (net (code "46") (name "CAM_D0_P") (class "Default")
      (node (ref "J4") (pin "8") (pinfunction "MIPI_CSI0_DATA0_P_8") (pintype "passive"))
    )
    (net (code "47") (name "CAM_D1_N") (class "Default")
      (node (ref "J4") (pin "16") (pinfunction "MIPI_CSI0_DATA1_M_16") (pintype "passive"))
    )
    (net (code "48") (name "CAM_D1_P") (class "Default")
      (node (ref "J4") (pin "14") (pinfunction "MIPI_CSI0_DATA1_P_14") (pintype "passive"))
    )
    (net (code "49") (name "CAM_ENABLE") (class "Default")
      (node (ref "TP22") (pin "1") (pintype "passive"))
      (node (ref "U8") (pin "14") (pinfunction "B6_14") (pintype "passive"))
    )
    (net (code "50") (name "CAM_LED_EN") (class "Default")
      (node (ref "TP21") (pin "1") (pintype "passive"))
      (node (ref "U8") (pin "15") (pinfunction "B5_15") (pintype "passive"))
    )
    (net (code "51") (name "CDC_MIC2_P") (class "Default")
      (node (ref "C34") (pin "1") (pinfunction "1_1") (pintype "passive"))
      (node (ref "R54") (pin "1") (pinfunction "1_1") (pintype "passive"))
    )
    (net (code "52") (name "CDC_MIC3_P") (class "Default")
      (node (ref "C35") (pin "1") (pinfunction "1_1") (pintype "passive"))
      (node (ref "R57") (pin "2") (pinfunction "2_2") (pintype "passive"))
    )
    (net (code "53") (name "CDC_MIC_BIAS1") (class "Default")
      (node (ref "J5") (pin "12") (pinfunction "CDC_MIC_BIAS1_12") (pintype "passive"))
      (node (ref "R121") (pin "2") (pinfunction "2_2") (pintype "passive"))
    )
    (net (code "54") (name "DRBD_SPKR+") (class "Default")
      (node (ref "J5") (pin "1") (pinfunction "SPKR+_1") (pintype "passive"))
    )
    (net (code "55") (name "DRBD_SPKR-") (class "Default")
      (node (ref "J5") (pin "2") (pinfunction "SPKR-_2") (pintype "passive"))
    )
    (net (code "56") (name "GND") (class "Default")
      (node (ref "C27") (pin "2") (pinfunction "2_2") (pintype "passive"))
      (node (ref "C28") (pin "1") (pinfunction "1_1") (pintype "passive"))
      (node (ref "C29") (pin "1") (pinfunction "1_1") (pintype "passive"))
      (node (ref "C30") (pin "2") (pinfunction "2_2") (pintype "passive"))
      (node (ref "C31") (pin "2") (pinfunction "2_2") (pintype "passive"))
      (node (ref "C32") (pin "1") (pinfunction "1_1") (pintype "passive"))
      (node (ref "C33") (pin "1") (pinfunction "1_1") (pintype "passive"))
      (node (ref "J3") (pin "1") (pinfunction "GND_1") (pintype "passive"))
      (node (ref "J3") (pin "2") (pinfunction "GND_2") (pintype "passive"))
      (node (ref "J3") (pin "39") (pinfunction "GND_39") (pintype "passive"))
      (node (ref "J3") (pin "40") (pinfunction "GND_40") (pintype "passive"))
      (node (ref "J4") (pin "12") (pinfunction "GND_12") (pintype "passive"))
      (node (ref "J4") (pin "13") (pinfunction "GND_13") (pintype "passive"))
      (node (ref "J4") (pin "18") (pinfunction "GND_18") (pintype "passive"))
      (node (ref "J4") (pin "19") (pinfunction "GND_19") (pintype "passive"))
      (node (ref "J4") (pin "24") (pinfunction "GND_24") (pintype "passive"))
      (node (ref "J4") (pin "25") (pinfunction "GND_25") (pintype "passive"))
      (node (ref "J4") (pin "30") (pinfunction "GND_30") (pintype "passive"))
      (node (ref "J4") (pin "31") (pinfunction "GND_31") (pintype "passive"))
      (node (ref "J4") (pin "37") (pinfunction "GND_37") (pintype "passive"))
      (node (ref "J4") (pin "40") (pinfunction "GND_40") (pintype "passive"))
      (node (ref "J4") (pin "43") (pinfunction "GND_43") (pintype "passive"))
      (node (ref "J4") (pin "46") (pinfunction "GND_46") (pintype "passive"))
      (node (ref "J4") (pin "49") (pinfunction "GND_49") (pintype "passive"))
      (node (ref "J4") (pin "52") (pinfunction "GND_52") (pintype "passive"))
      (node (ref "J4") (pin "55") (pinfunction "GND_55") (pintype "passive"))
      (node (ref "J4") (pin "58") (pinfunction "GND_58") (pintype "passive"))
      (node (ref "J4") (pin "6") (pinfunction "GND_6") (pintype "passive"))
      (node (ref "J5") (pin "4") (pinfunction "GND_4") (pintype "passive"))
      (node (ref "R122") (pin "1") (pinfunction "1_1") (pintype "passive"))
      (node (ref "R54") (pin "2") (pinfunction "2_2") (pintype "passive"))
      (node (ref "R55") (pin "2") (pinfunction "2_2") (pintype "passive"))
      (node (ref "R56") (pin "1") (pinfunction "1_1") (pintype "passive"))
      (node (ref "R57") (pin "1") (pinfunction "1_1") (pintype "passive"))
      (node (ref "U8") (pin "11") (pinfunction "GND_11") (pintype "passive"))
      (node (ref "U9") (pin "11") (pinfunction "GND_11") (pintype "passive"))
    )
    (net (code "57") (name "GND_CFILT") (class "Default")
      (node (ref "J5") (pin "5") (pinfunction "CDC_GND_FILT_5") (pintype "passive"))
    )
    (net (code "58") (name "GYRO_INT1") (class "Default")
      (node (ref "TP23") (pin "1") (pintype "passive"))
      (node (ref "U8") (pin "13") (pinfunction "B7_13") (pintype "passive"))
    )
    (net (code "59") (name "GYRO_INT2") (class "Default")
      (node (ref "TP26") (pin "1") (pintype "passive"))
      (node (ref "U8") (pin "12") (pinfunction "B8_12") (pintype "passive"))
    )
    (net (code "60") (name "I2C0_SCL") (class "Default")
      (node (ref "TP15") (pin "1") (pintype "passive"))
      (node (ref "U8") (pin "20") (pinfunction "B1_20") (pintype "passive"))
    )
    (net (code "61") (name "I2C0_SDA") (class "Default")
      (node (ref "TP17") (pin "1") (pintype "passive"))
      (node (ref "U8") (pin "18") (pinfunction "B2_18") (pintype "passive"))
    )
    (net (code "62") (name "I2C1_SCL") (class "Default")
      (node (ref "TP33") (pin "1") (pintype "passive"))
      (node (ref "U9") (pin "20") (pinfunction "B1_20") (pintype "passive"))
    )
    (net (code "63") (name "I2C1_SDA") (class "Default")
      (node (ref "TP34") (pin "1") (pintype "passive"))
      (node (ref "U9") (pin "18") (pinfunction "B2_18") (pintype "passive"))
    )
    (net (code "64") (name "I2C2_SCL") (class "Default")
      (node (ref "TP18") (pin "1") (pintype "passive"))
      (node (ref "U8") (pin "17") (pinfunction "B3_17") (pintype "passive"))
    )
    (net (code "65") (name "I2C2_SDA") (class "Default")
      (node (ref "TP20") (pin "1") (pintype "passive"))
      (node (ref "U8") (pin "16") (pinfunction "B4_16") (pintype "passive"))
    )
    (net (code "66") (name "LED_CNTRL") (class "Default")
      (node (ref "TP36") (pin "1") (pintype "passive"))
      (node (ref "U9") (pin "16") (pinfunction "B4_16") (pintype "passive"))
    )
    (net (code "67") (name "LS_EXP_1P8") (class "Default")
      (node (ref "C27") (pin "1") (pinfunction "1_1") (pintype "passive"))
      (node (ref "C29") (pin "2") (pinfunction "2_2") (pintype "passive"))
      (node (ref "C30") (pin "1") (pinfunction "1_1") (pintype "passive"))
      (node (ref "C31") (pin "1") (pinfunction "1_1") (pintype "passive"))
      (node (ref "C33") (pin "2") (pinfunction "2_2") (pintype "passive"))
      (node (ref "FUSE3") (pin "1") (pinfunction "1_1") (pintype "passive"))
      (node (ref "R53") (pin "1") (pinfunction "1_1") (pintype "passive"))
      (node (ref "U8") (pin "10") (pinfunction "OE_10") (pintype "passive"))
      (node (ref "U8") (pin "2") (pinfunction "Vcca_2") (pintype "passive"))
      (node (ref "U9") (pin "10") (pinfunction "OE_10") (pintype "passive"))
      (node (ref "U9") (pin "2") (pinfunction "Vcca_2") (pintype "passive"))
    )
    (net (code "68") (name "LineIn_Detect") (class "Default")
      (node (ref "R52") (pin "1") (pinfunction "1_1") (pintype "passive"))
    )
    (net (code "69") (name "Net-(R53-Pad2)") (class "Default")
      (node (ref "R53") (pin "2") (pinfunction "2_2") (pintype "passive"))
      (node (ref "TP30") (pin "1") (pintype "passive"))
    )
    (net (code "70") (name "PWM_CNTRL") (class "Default")
      (node (ref "TP35") (pin "1") (pintype "passive"))
      (node (ref "U9") (pin "17") (pinfunction "B3_17") (pintype "passive"))
    )
    (net (code "71") (name "SPI0_CLK") (class "Default")
      (node (ref "TP37") (pin "1") (pintype "passive"))
      (node (ref "U9") (pin "15") (pinfunction "B5_15") (pintype "passive"))
    )
    (net (code "72") (name "SPI0_CSn") (class "Default")
      (node (ref "TP39") (pin "1") (pintype "passive"))
      (node (ref "U9") (pin "13") (pinfunction "B7_13") (pintype "passive"))
    )
    (net (code "73") (name "SPI0_MISO") (class "Default")
      (node (ref "TP38") (pin "1") (pintype "passive"))
      (node (ref "U9") (pin "14") (pinfunction "B6_14") (pintype "passive"))
    )
    (net (code "74") (name "unconnected-(J3-LS_EXP_MI2S_DATA0-Pad20)") (class "Default")
      (node (ref "J3") (pin "20") (pinfunction "LS_EXP_MI2S_DATA0_20") (pintype "passive+no_connect"))
    )
    (net (code "75") (name "unconnected-(J3-LS_EXP_MI2S_SCK-Pad18)") (class "Default")
      (node (ref "J3") (pin "18") (pinfunction "LS_EXP_MI2S_SCK_18") (pintype "passive+no_connect"))
    )
    (net (code "76") (name "unconnected-(J3-LS_EXP_MI2S_WS-Pad16)") (class "Default")
      (node (ref "J3") (pin "16") (pinfunction "LS_EXP_MI2S_WS_16") (pintype "passive+no_connect"))
    )
    (net (code "77") (name "unconnected-(J3-N.C.-Pad22)") (class "Default")
      (node (ref "J3") (pin "22") (pinfunction "N.C._22") (pintype "passive+no_connect"))
    )
    (net (code "78") (name "unconnected-(J3-PHONE_ON_N-Pad4)") (class "Default")
      (node (ref "J3") (pin "4") (pinfunction "PHONE_ON_N_4") (pintype "passive+no_connect"))
    )
    (net (code "79") (name "unconnected-(J3-PM_RESIN_N-Pad6)") (class "Default")
      (node (ref "J3") (pin "6") (pinfunction "PM_RESIN_N_6") (pintype "passive+no_connect"))
    )
    (net (code "80") (name "unconnected-(J3-SYS_5P0-Pad37)") (class "Default")
      (node (ref "J3") (pin "37") (pinfunction "SYS_5P0_37") (pintype "passive"))
    )
    (net (code "81") (name "unconnected-(J3-UART0_CTS_N-Pad3)") (class "Default")
      (node (ref "J3") (pin "3") (pinfunction "UART0_CTS_N_3") (pintype "passive+no_connect"))
    )
    (net (code "82") (name "unconnected-(J3-UART0_RTS_N-Pad9)") (class "Default")
      (node (ref "J3") (pin "9") (pinfunction "UART0_RTS_N_9") (pintype "passive+no_connect"))
    )
    (net (code "83") (name "unconnected-(J3-UART0_RX-Pad7)") (class "Default")
      (node (ref "J3") (pin "7") (pinfunction "UART0_RX_7") (pintype "passive+no_connect"))
    )
    (net (code "84") (name "unconnected-(J3-UART0_TX-Pad5)") (class "Default")
      (node (ref "J3") (pin "5") (pinfunction "UART0_TX_5") (pintype "passive+no_connect"))
    )
    (net (code "85") (name "unconnected-(J4-CSI1_MCLK-Pad17)") (class "Default")
      (node (ref "J4") (pin "17") (pinfunction "CSI1_MCLK_17") (pintype "passive"))
    )
    (net (code "86") (name "unconnected-(J4-I2C3_SCL-Pad36)") (class "Default")
      (node (ref "J4") (pin "36") (pinfunction "I2C3_SCL_36") (pintype "passive+no_connect"))
    )
    (net (code "87") (name "unconnected-(J4-I2C3_SDA-Pad38)") (class "Default")
      (node (ref "J4") (pin "38") (pinfunction "I2C3_SDA_38") (pintype "passive+no_connect"))
    )
    (net (code "88") (name "unconnected-(J4-MIPI_CSI0_DATA2_M-Pad22)") (class "Default")
      (node (ref "J4") (pin "22") (pinfunction "MIPI_CSI0_DATA2_M_22") (pintype "passive+no_connect"))
    )
    (net (code "89") (name "unconnected-(J4-MIPI_CSI0_DATA2_P-Pad20)") (class "Default")
      (node (ref "J4") (pin "20") (pinfunction "MIPI_CSI0_DATA2_P_20") (pintype "passive+no_connect"))
    )
    (net (code "90") (name "unconnected-(J4-MIPI_CSI0_DATA3_M-Pad28)") (class "Default")
      (node (ref "J4") (pin "28") (pinfunction "MIPI_CSI0_DATA3_M_28") (pintype "passive+no_connect"))
    )
    (net (code "91") (name "unconnected-(J4-MIPI_CSI0_DATA3_P-Pad26)") (class "Default")
      (node (ref "J4") (pin "26") (pinfunction "MIPI_CSI0_DATA3_P_26") (pintype "passive+no_connect"))
    )
    (net (code "92") (name "unconnected-(J4-MIPI_CSI1_CLK_M-Pad56)") (class "Default")
      (node (ref "J4") (pin "56") (pinfunction "MIPI_CSI1_CLK_M_56") (pintype "passive+no_connect"))
    )
    (net (code "93") (name "unconnected-(J4-MIPI_CSI1_CLK_P-Pad54)") (class "Default")
      (node (ref "J4") (pin "54") (pinfunction "MIPI_CSI1_CLK_P_54") (pintype "passive+no_connect"))
    )
    (net (code "94") (name "unconnected-(J4-MIPI_CSI1_DATA0_M-Pad44)") (class "Default")
      (node (ref "J4") (pin "44") (pinfunction "MIPI_CSI1_DATA0_M_44") (pintype "passive+no_connect"))
    )
    (net (code "95") (name "unconnected-(J4-MIPI_CSI1_DATA0_M-Pad50)") (class "Default")
      (node (ref "J4") (pin "50") (pinfunction "MIPI_CSI1_DATA0_M_50") (pintype "passive+no_connect"))
    )
    (net (code "96") (name "unconnected-(J4-MIPI_CSI1_DATA0_P-Pad42)") (class "Default")
      (node (ref "J4") (pin "42") (pinfunction "MIPI_CSI1_DATA0_P_42") (pintype "passive+no_connect"))
    )
    (net (code "97") (name "unconnected-(J4-MIPI_CSI1_DATA1_P-Pad48)") (class "Default")
      (node (ref "J4") (pin "48") (pinfunction "MIPI_CSI1_DATA1_P_48") (pintype "passive+no_connect"))
    )
    (net (code "98") (name "unconnected-(J4-MIPI_DSI0_CLK_M_EXP_CONN-Pad23)") (class "Default")
      (node (ref "J4") (pin "23") (pinfunction "MIPI_DSI0_CLK_M_EXP_CONN_23") (pintype "passive+no_connect"))
    )
    (net (code "99") (name "unconnected-(J4-MIPI_DSI0_CLK_P_EXP_CONN-Pad21)") (class "Default")
      (node (ref "J4") (pin "21") (pinfunction "MIPI_DSI0_CLK_P_EXP_CONN_21") (pintype "passive+no_connect"))
    )
    (net (code "100") (name "unconnected-(J4-MIPI_DSI0_DATA0_M_EXP_CONN-Pad29)") (class "Default")
      (node (ref "J4") (pin "29") (pinfunction "MIPI_DSI0_DATA0_M_EXP_CONN_29") (pintype "passive+no_connect"))
    )
    (net (code "101") (name "unconnected-(J4-MIPI_DSI0_DATA0_P_EXP_CONN-Pad27)") (class "Default")
      (node (ref "J4") (pin "27") (pinfunction "MIPI_DSI0_DATA0_P_EXP_CONN_27") (pintype "passive+no_connect"))
    )
    (net (code "102") (name "unconnected-(J4-MIPI_DSI0_DATA1_M_EXP_CONN-Pad35)") (class "Default")
      (node (ref "J4") (pin "35") (pinfunction "MIPI_DSI0_DATA1_M_EXP_CONN_35") (pintype "passive+no_connect"))
    )
    (net (code "103") (name "unconnected-(J4-MIPI_DSI0_DATA1_P_EXP_CONN-Pad33)") (class "Default")
      (node (ref "J4") (pin "33") (pinfunction "MIPI_DSI0_DATA1_P_EXP_CONN_33") (pintype "passive+no_connect"))
    )
    (net (code "104") (name "unconnected-(J4-MIPI_DSI0_DATA2_M_EXP_CONN-Pad41)") (class "Default")
      (node (ref "J4") (pin "41") (pinfunction "MIPI_DSI0_DATA2_M_EXP_CONN_41") (pintype "passive+no_connect"))
    )
    (net (code "105") (name "unconnected-(J4-MIPI_DSI0_DATA2_P_EXP_CONN-Pad39)") (class "Default")
      (node (ref "J4") (pin "39") (pinfunction "MIPI_DSI0_DATA2_P_EXP_CONN_39") (pintype "passive+no_connect"))
    )
    (net (code "106") (name "unconnected-(J4-MIPI_DSI0_DATA3_M_EXP_CONN-Pad47)") (class "Default")
      (node (ref "J4") (pin "47") (pinfunction "MIPI_DSI0_DATA3_M_EXP_CONN_47") (pintype "passive+no_connect"))
    )
    (net (code "107") (name "unconnected-(J4-MIPI_DSI0_DATA3_P_EXP_CONN-Pad45)") (class "Default")
      (node (ref "J4") (pin "45") (pinfunction "MIPI_DSI0_DATA3_P_EXP_CONN_45") (pintype "passive+no_connect"))
    )
    (net (code "108") (name "unconnected-(J4-N.C.-Pad3)") (class "Default")
      (node (ref "J4") (pin "3") (pinfunction "N.C._3") (pintype "passive+no_connect"))
    )
    (net (code "109") (name "unconnected-(J4-N.C.-Pad5)") (class "Default")
      (node (ref "J4") (pin "5") (pinfunction "N.C._5") (pintype "passive+no_connect"))
    )
    (net (code "110") (name "unconnected-(J4-N.C.-Pad57)") (class "Default")
      (node (ref "J4") (pin "57") (pinfunction "N.C._57") (pintype "passive+no_connect"))
    )
    (net (code "111") (name "unconnected-(J4-N.C.-Pad59)") (class "Default")
      (node (ref "J4") (pin "59") (pinfunction "N.C._59") (pintype "passive+no_connect"))
    )
    (net (code "112") (name "unconnected-(J4-N.C.-Pad60)") (class "Default")
      (node (ref "J4") (pin "60") (pinfunction "N.C._60") (pintype "passive+no_connect"))
    )
    (net (code "113") (name "unconnected-(J4-USB_HS_D_M_EXP-Pad53)") (class "Default")
      (node (ref "J4") (pin "53") (pinfunction "USB_HS_D_M_EXP_53") (pintype "passive+no_connect"))
    )
    (net (code "114") (name "unconnected-(J4-USB_HS_D_P_EXP-Pad51)") (class "Default")
      (node (ref "J4") (pin "51") (pinfunction "USB_HS_D_P_EXP_51") (pintype "passive+no_connect"))
    )
    (net (code "115") (name "unconnected-(J5-CDC_HPH_L-Pad10)") (class "Default")
      (node (ref "J5") (pin "10") (pinfunction "CDC_HPH_L_10") (pintype "passive+no_connect"))
    )
    (net (code "116") (name "unconnected-(J5-CDC_HPH_R-Pad8)") (class "Default")
      (node (ref "J5") (pin "8") (pinfunction "CDC_HPH_R_8") (pintype "passive+no_connect"))
    )
    (net (code "117") (name "unconnected-(J5-FM_RX_ANT-Pad15)") (class "Default")
      (node (ref "J5") (pin "15") (pinfunction "FM_RX_ANT_15") (pintype "passive+no_connect"))
    )
    (net (code "118") (name "unconnected-(J5-N.C.-Pad13)") (class "Default")
      (node (ref "J5") (pin "13") (pinfunction "N.C._13") (pintype "passive+no_connect"))
    )
    (net (code "119") (name "unconnected-(J5-N.C.-Pad14)") (class "Default")
      (node (ref "J5") (pin "14") (pinfunction "N.C._14") (pintype "passive+no_connect"))
    )
    (net (code "120") (name "unconnected-(J5-N.C.-Pad16)") (class "Default")
      (node (ref "J5") (pin "16") (pinfunction "N.C._16") (pintype "passive+no_connect"))
    )
    (net (code "121") (name "unconnected-(J5-VPH_PWR_3V7-Pad3)") (class "Default")
      (node (ref "J5") (pin "3") (pinfunction "VPH_PWR_3V7_3") (pintype "passive+no_connect"))
    )
  )
)
